# Backplane.net
KiCad netlist of a schematic drawn in EAGLE
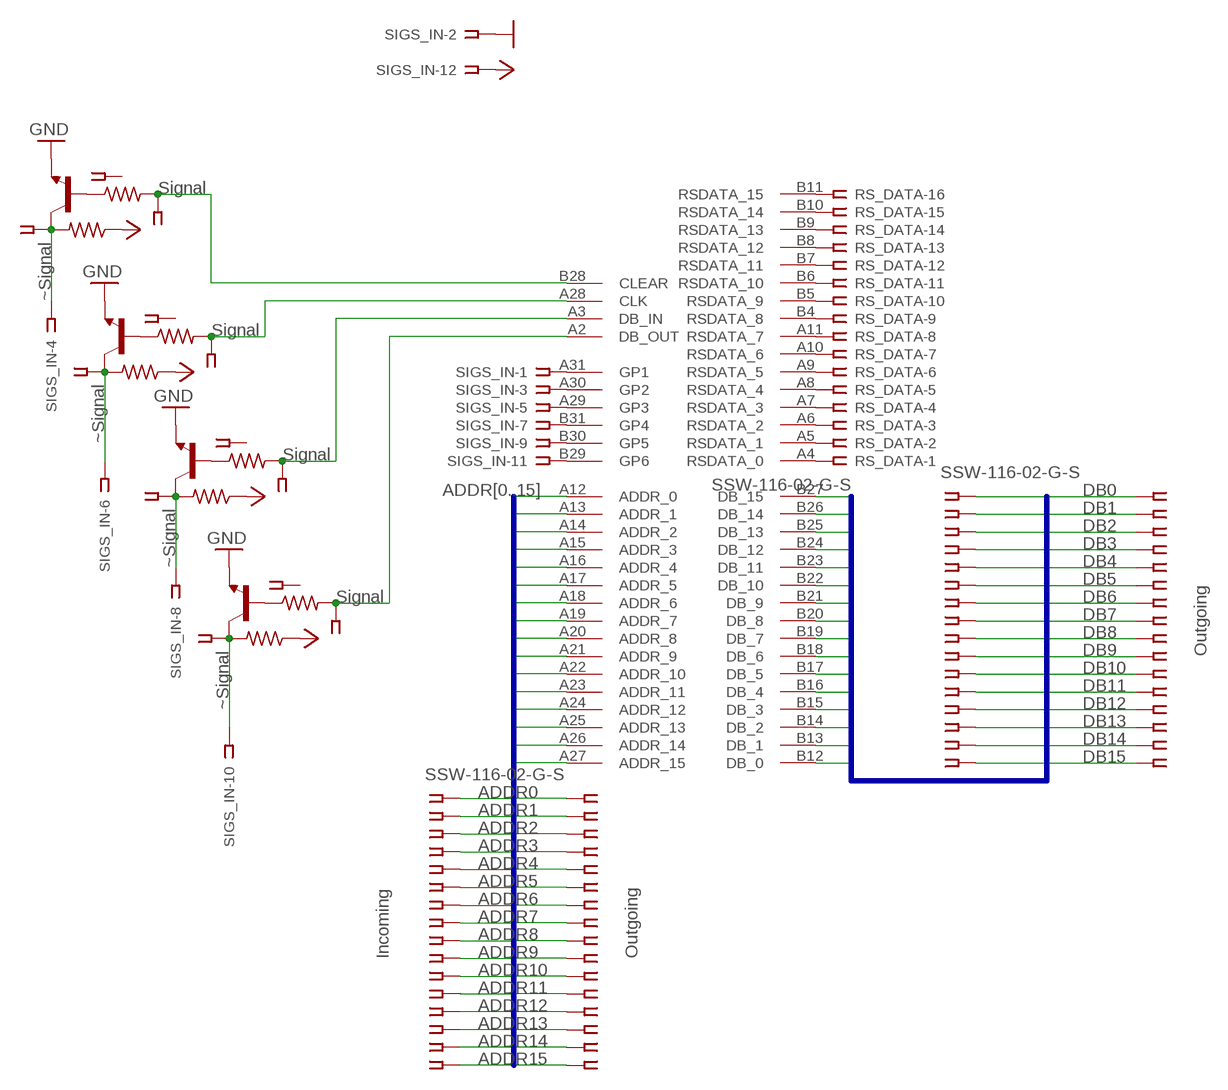
[diagram p0: schematic, sheet 1]

(export (version "E")
  (design (tool "Eeschema 10.0.6"))
  (components
    (comp (ref "ADDR_INCOMING")
      (value "SSW-116-02-G-S")
      (footprint "eagle-import:SSW-116-02-G-S")
      (fields (field (name "MF") "Samtec Inc."))
      (libsource (lib "eagle-import") (part "SSW-116-02-G-S"))
    )
    (comp (ref "ADDR_OUTGOING")
      (value "SSW-116-02-G-S-RA")
      (footprint "eagle-import:SSW-116-02-G-S-RA")
      (fields (field (name "MF") "Samtec Inc."))
      (libsource (lib "eagle-import") (part "SSW-116-02-G-S-RA"))
    )
    (comp (ref "DB_INCOMING")
      (value "SSW-116-02-G-S")
      (footprint "eagle-import:SSW-116-02-G-S")
      (fields (field (name "MF") "Samtec Inc."))
      (libsource (lib "eagle-import") (part "SSW-116-02-G-S"))
    )
    (comp (ref "DB_OUTGOING")
      (value "SSW-116-02-G-S-RA")
      (footprint "eagle-import:SSW-116-02-G-S-RA")
      (fields (field (name "MF") "Samtec Inc."))
      (libsource (lib "eagle-import") (part "SSW-116-02-G-S-RA"))
    )
    (comp (ref "NO_INVERT_JUMPER")
      (value "SSW-103-02-G-S")
      (footprint "eagle-import:SSW-103-02-G-S")
      (fields (field (name "MF") "Samtec Inc."))
      (libsource (lib "eagle-import") (part "SSW-103-02-G-S"))
    )
    (comp (ref "NO_INVERT_JUMPER1")
      (value "SSW-103-02-G-S")
      (footprint "eagle-import:SSW-103-02-G-S")
      (fields (field (name "MF") "Samtec Inc."))
      (libsource (lib "eagle-import") (part "SSW-103-02-G-S"))
    )
    (comp (ref "NO_INVERT_JUMPER2")
      (value "SSW-103-02-G-S")
      (footprint "eagle-import:SSW-103-02-G-S")
      (fields (field (name "MF") "Samtec Inc."))
      (libsource (lib "eagle-import") (part "SSW-103-02-G-S"))
    )
    (comp (ref "NO_INVERT_JUMPER3")
      (value "SSW-103-02-G-S")
      (footprint "eagle-import:SSW-103-02-G-S")
      (fields (field (name "MF") "Samtec Inc."))
      (libsource (lib "eagle-import") (part "SSW-103-02-G-S"))
    )
    (comp (ref "R1")
      (value "~220")
      (footprint "eagle-import:0204_7")
      (libsource (lib "eagle-import") (part "R-US_0204/7"))
    )
    (comp (ref "R2")
      (value "~220")
      (footprint "eagle-import:0204_7")
      (libsource (lib "eagle-import") (part "R-US_0204/7"))
    )
    (comp (ref "R3")
      (value "~220")
      (footprint "eagle-import:0204_7")
      (libsource (lib "eagle-import") (part "R-US_0204/7"))
    )
    (comp (ref "R4")
      (value "~220")
      (footprint "eagle-import:0204_7")
      (libsource (lib "eagle-import") (part "R-US_0204/7"))
    )
    (comp (ref "R5")
      (value "~220")
      (footprint "eagle-import:0204_7")
      (libsource (lib "eagle-import") (part "R-US_0204/7"))
    )
    (comp (ref "R6")
      (value "~220")
      (footprint "eagle-import:0204_7")
      (libsource (lib "eagle-import") (part "R-US_0204/7"))
    )
    (comp (ref "R7")
      (value "~220")
      (footprint "eagle-import:0204_7")
      (libsource (lib "eagle-import") (part "R-US_0204/7"))
    )
    (comp (ref "R8")
      (value "~220")
      (footprint "eagle-import:0204_7")
      (libsource (lib "eagle-import") (part "R-US_0204/7"))
    )
    (comp (ref "RS_DATA")
      (value "SSW-116-02-G-S")
      (footprint "eagle-import:SSW-116-02-G-S")
      (fields (field (name "MF") "Samtec Inc."))
      (libsource (lib "eagle-import") (part "SSW-116-02-G-S"))
    )
    (comp (ref "SIGS_IN")
      (value "SSW-106-02-G-D")
      (footprint "eagle-import:SSW-106-02-G-D")
      (fields (field (name "MF") "Samtec Inc."))
      (libsource (lib "eagle-import") (part "SSW-106-02-G-D"))
    )
    (comp (ref "T1")
      (value "2N3565")
      (footprint "eagle-import:TO92")
      (libsource (lib "eagle-import") (part "2N3565"))
    )
    (comp (ref "T2")
      (value "2N3565")
      (footprint "eagle-import:TO92")
      (libsource (lib "eagle-import") (part "2N3565"))
    )
    (comp (ref "T3")
      (value "2N3565")
      (footprint "eagle-import:TO92")
      (libsource (lib "eagle-import") (part "2N3565"))
    )
    (comp (ref "T4")
      (value "2N3565")
      (footprint "eagle-import:TO92")
      (libsource (lib "eagle-import") (part "2N3565"))
    )
    (comp (ref "U$1")
      (value "BACKPLATE_INTERFACEHEADER")
      (footprint "eagle-import:PCI_INTERFACE")
      (libsource (lib "eagle-import") (part "BACKPLATE_INTERFACEHEADER"))
    )
  )
  (nets
    (net (code "1") (name "/ADDR0") (class "Default")
      (node (ref "ADDR_INCOMING") (pin "1") (pinfunction "1_1") (pintype "passive"))
      (node (ref "ADDR_OUTGOING") (pin "16") (pinfunction "1_16") (pintype "passive"))
      (node (ref "U$1") (pin "A12") (pinfunction "ADDR_0_A12") (pintype "bidirectional"))
    )
    (net (code "2") (name "/ADDR1") (class "Default")
      (node (ref "ADDR_INCOMING") (pin "2") (pinfunction "1_2") (pintype "passive"))
      (node (ref "ADDR_OUTGOING") (pin "15") (pinfunction "1_15") (pintype "passive"))
      (node (ref "U$1") (pin "A13") (pinfunction "ADDR_1_A13") (pintype "bidirectional"))
    )
    (net (code "3") (name "/ADDR2") (class "Default")
      (node (ref "ADDR_INCOMING") (pin "3") (pinfunction "1_3") (pintype "passive"))
      (node (ref "ADDR_OUTGOING") (pin "14") (pinfunction "1_14") (pintype "passive"))
      (node (ref "U$1") (pin "A14") (pinfunction "ADDR_2_A14") (pintype "bidirectional"))
    )
    (net (code "4") (name "/ADDR3") (class "Default")
      (node (ref "ADDR_INCOMING") (pin "4") (pinfunction "1_4") (pintype "passive"))
      (node (ref "ADDR_OUTGOING") (pin "13") (pinfunction "1_13") (pintype "passive"))
      (node (ref "U$1") (pin "A15") (pinfunction "ADDR_3_A15") (pintype "bidirectional"))
    )
    (net (code "5") (name "/ADDR4") (class "Default")
      (node (ref "ADDR_INCOMING") (pin "5") (pinfunction "1_5") (pintype "passive"))
      (node (ref "ADDR_OUTGOING") (pin "12") (pinfunction "1_12") (pintype "passive"))
      (node (ref "U$1") (pin "A16") (pinfunction "ADDR_4_A16") (pintype "bidirectional"))
    )
    (net (code "6") (name "/ADDR5") (class "Default")
      (node (ref "ADDR_INCOMING") (pin "6") (pinfunction "1_6") (pintype "passive"))
      (node (ref "ADDR_OUTGOING") (pin "11") (pinfunction "1_11") (pintype "passive"))
      (node (ref "U$1") (pin "A17") (pinfunction "ADDR_5_A17") (pintype "bidirectional"))
    )
    (net (code "7") (name "/ADDR6") (class "Default")
      (node (ref "ADDR_INCOMING") (pin "7") (pinfunction "1_7") (pintype "passive"))
      (node (ref "ADDR_OUTGOING") (pin "10") (pinfunction "1_10") (pintype "passive"))
      (node (ref "U$1") (pin "A18") (pinfunction "ADDR_6_A18") (pintype "bidirectional"))
    )
    (net (code "8") (name "/ADDR7") (class "Default")
      (node (ref "ADDR_INCOMING") (pin "8") (pinfunction "1_8") (pintype "passive"))
      (node (ref "ADDR_OUTGOING") (pin "9") (pinfunction "1_9") (pintype "passive"))
      (node (ref "U$1") (pin "A19") (pinfunction "ADDR_7_A19") (pintype "bidirectional"))
    )
    (net (code "9") (name "/ADDR8") (class "Default")
      (node (ref "ADDR_INCOMING") (pin "9") (pinfunction "1_9") (pintype "passive"))
      (node (ref "ADDR_OUTGOING") (pin "8") (pinfunction "1_8") (pintype "passive"))
      (node (ref "U$1") (pin "A20") (pinfunction "ADDR_8_A20") (pintype "bidirectional"))
    )
    (net (code "10") (name "/ADDR9") (class "Default")
      (node (ref "ADDR_INCOMING") (pin "10") (pinfunction "1_10") (pintype "passive"))
      (node (ref "ADDR_OUTGOING") (pin "7") (pinfunction "1_7") (pintype "passive"))
      (node (ref "U$1") (pin "A21") (pinfunction "ADDR_9_A21") (pintype "bidirectional"))
    )
    (net (code "11") (name "/ADDR10") (class "Default")
      (node (ref "ADDR_INCOMING") (pin "11") (pinfunction "1_11") (pintype "passive"))
      (node (ref "ADDR_OUTGOING") (pin "6") (pinfunction "1_6") (pintype "passive"))
      (node (ref "U$1") (pin "A22") (pinfunction "ADDR_10_A22") (pintype "bidirectional"))
    )
    (net (code "12") (name "/ADDR11") (class "Default")
      (node (ref "ADDR_INCOMING") (pin "12") (pinfunction "1_12") (pintype "passive"))
      (node (ref "ADDR_OUTGOING") (pin "5") (pinfunction "1_5") (pintype "passive"))
      (node (ref "U$1") (pin "A23") (pinfunction "ADDR_11_A23") (pintype "bidirectional"))
    )
    (net (code "13") (name "/ADDR12") (class "Default")
      (node (ref "ADDR_INCOMING") (pin "13") (pinfunction "1_13") (pintype "passive"))
      (node (ref "ADDR_OUTGOING") (pin "4") (pinfunction "1_4") (pintype "passive"))
      (node (ref "U$1") (pin "A24") (pinfunction "ADDR_12_A24") (pintype "bidirectional"))
    )
    (net (code "14") (name "/ADDR13") (class "Default")
      (node (ref "ADDR_INCOMING") (pin "14") (pinfunction "1_14") (pintype "passive"))
      (node (ref "ADDR_OUTGOING") (pin "3") (pinfunction "1_3") (pintype "passive"))
      (node (ref "U$1") (pin "A25") (pinfunction "ADDR_13_A25") (pintype "bidirectional"))
    )
    (net (code "15") (name "/ADDR14") (class "Default")
      (node (ref "ADDR_INCOMING") (pin "15") (pinfunction "1_15") (pintype "passive"))
      (node (ref "ADDR_OUTGOING") (pin "2") (pinfunction "1_2") (pintype "passive"))
      (node (ref "U$1") (pin "A26") (pinfunction "ADDR_14_A26") (pintype "bidirectional"))
    )
    (net (code "16") (name "/ADDR15") (class "Default")
      (node (ref "ADDR_INCOMING") (pin "16") (pinfunction "1_16") (pintype "passive"))
      (node (ref "ADDR_OUTGOING") (pin "1") (pinfunction "1_1") (pintype "passive"))
      (node (ref "U$1") (pin "A27") (pinfunction "ADDR_15_A27") (pintype "bidirectional"))
    )
    (net (code "17") (name "/DB0") (class "Default")
      (node (ref "DB_INCOMING") (pin "1") (pinfunction "1_1") (pintype "passive"))
      (node (ref "DB_OUTGOING") (pin "16") (pinfunction "1_16") (pintype "passive"))
      (node (ref "U$1") (pin "B12") (pinfunction "DB_0_B12") (pintype "bidirectional"))
    )
    (net (code "18") (name "/DB1") (class "Default")
      (node (ref "DB_INCOMING") (pin "2") (pinfunction "1_2") (pintype "passive"))
      (node (ref "DB_OUTGOING") (pin "15") (pinfunction "1_15") (pintype "passive"))
      (node (ref "U$1") (pin "B13") (pinfunction "DB_1_B13") (pintype "bidirectional"))
    )
    (net (code "19") (name "/DB2") (class "Default")
      (node (ref "DB_INCOMING") (pin "3") (pinfunction "1_3") (pintype "passive"))
      (node (ref "DB_OUTGOING") (pin "14") (pinfunction "1_14") (pintype "passive"))
      (node (ref "U$1") (pin "B14") (pinfunction "DB_2_B14") (pintype "bidirectional"))
    )
    (net (code "20") (name "/DB3") (class "Default")
      (node (ref "DB_INCOMING") (pin "4") (pinfunction "1_4") (pintype "passive"))
      (node (ref "DB_OUTGOING") (pin "13") (pinfunction "1_13") (pintype "passive"))
      (node (ref "U$1") (pin "B15") (pinfunction "DB_3_B15") (pintype "bidirectional"))
    )
    (net (code "21") (name "/DB4") (class "Default")
      (node (ref "DB_INCOMING") (pin "5") (pinfunction "1_5") (pintype "passive"))
      (node (ref "DB_OUTGOING") (pin "12") (pinfunction "1_12") (pintype "passive"))
      (node (ref "U$1") (pin "B16") (pinfunction "DB_4_B16") (pintype "bidirectional"))
    )
    (net (code "22") (name "/DB5") (class "Default")
      (node (ref "DB_INCOMING") (pin "6") (pinfunction "1_6") (pintype "passive"))
      (node (ref "DB_OUTGOING") (pin "11") (pinfunction "1_11") (pintype "passive"))
      (node (ref "U$1") (pin "B17") (pinfunction "DB_5_B17") (pintype "bidirectional"))
    )
    (net (code "23") (name "/DB6") (class "Default")
      (node (ref "DB_INCOMING") (pin "7") (pinfunction "1_7") (pintype "passive"))
      (node (ref "DB_OUTGOING") (pin "10") (pinfunction "1_10") (pintype "passive"))
      (node (ref "U$1") (pin "B18") (pinfunction "DB_6_B18") (pintype "bidirectional"))
    )
    (net (code "24") (name "/DB7") (class "Default")
      (node (ref "DB_INCOMING") (pin "8") (pinfunction "1_8") (pintype "passive"))
      (node (ref "DB_OUTGOING") (pin "9") (pinfunction "1_9") (pintype "passive"))
      (node (ref "U$1") (pin "B19") (pinfunction "DB_7_B19") (pintype "bidirectional"))
    )
    (net (code "25") (name "/DB8") (class "Default")
      (node (ref "DB_INCOMING") (pin "9") (pinfunction "1_9") (pintype "passive"))
      (node (ref "DB_OUTGOING") (pin "8") (pinfunction "1_8") (pintype "passive"))
      (node (ref "U$1") (pin "B20") (pinfunction "DB_8_B20") (pintype "bidirectional"))
    )
    (net (code "26") (name "/DB9") (class "Default")
      (node (ref "DB_INCOMING") (pin "10") (pinfunction "1_10") (pintype "passive"))
      (node (ref "DB_OUTGOING") (pin "7") (pinfunction "1_7") (pintype "passive"))
      (node (ref "U$1") (pin "B21") (pinfunction "DB_9_B21") (pintype "bidirectional"))
    )
    (net (code "27") (name "/DB10") (class "Default")
      (node (ref "DB_INCOMING") (pin "11") (pinfunction "1_11") (pintype "passive"))
      (node (ref "DB_OUTGOING") (pin "6") (pinfunction "1_6") (pintype "passive"))
      (node (ref "U$1") (pin "B22") (pinfunction "DB_10_B22") (pintype "bidirectional"))
    )
    (net (code "28") (name "/DB11") (class "Default")
      (node (ref "DB_INCOMING") (pin "12") (pinfunction "1_12") (pintype "passive"))
      (node (ref "DB_OUTGOING") (pin "5") (pinfunction "1_5") (pintype "passive"))
      (node (ref "U$1") (pin "B23") (pinfunction "DB_11_B23") (pintype "bidirectional"))
    )
    (net (code "29") (name "/DB12") (class "Default")
      (node (ref "DB_INCOMING") (pin "13") (pinfunction "1_13") (pintype "passive"))
      (node (ref "DB_OUTGOING") (pin "4") (pinfunction "1_4") (pintype "passive"))
      (node (ref "U$1") (pin "B24") (pinfunction "DB_12_B24") (pintype "bidirectional"))
    )
    (net (code "30") (name "/DB13") (class "Default")
      (node (ref "DB_INCOMING") (pin "14") (pinfunction "1_14") (pintype "passive"))
      (node (ref "DB_OUTGOING") (pin "3") (pinfunction "1_3") (pintype "passive"))
      (node (ref "U$1") (pin "B25") (pinfunction "DB_13_B25") (pintype "bidirectional"))
    )
    (net (code "31") (name "/DB14") (class "Default")
      (node (ref "DB_INCOMING") (pin "15") (pinfunction "1_15") (pintype "passive"))
      (node (ref "DB_OUTGOING") (pin "2") (pinfunction "1_2") (pintype "passive"))
      (node (ref "U$1") (pin "B26") (pinfunction "DB_14_B26") (pintype "bidirectional"))
    )
    (net (code "32") (name "/DB15") (class "Default")
      (node (ref "DB_INCOMING") (pin "16") (pinfunction "1_16") (pintype "passive"))
      (node (ref "DB_OUTGOING") (pin "1") (pinfunction "1_1") (pintype "passive"))
      (node (ref "U$1") (pin "B27") (pinfunction "DB_15_B27") (pintype "bidirectional"))
    )
    (net (code "33") (name "GND") (class "Default")
      (node (ref "SIGS_IN") (pin "2") (pinfunction "1_2") (pintype "passive"))
      (node (ref "T1") (pin "3") (pinfunction "E_3") (pintype "passive"))
      (node (ref "T2") (pin "3") (pinfunction "E_3") (pintype "passive"))
      (node (ref "T3") (pin "3") (pinfunction "E_3") (pintype "passive"))
      (node (ref "T4") (pin "3") (pinfunction "E_3") (pintype "passive"))
    )
    (net (code "34") (name "Net-(NO_INVERT_JUMPER1B-1)") (class "Default")
      (node (ref "NO_INVERT_JUMPER1") (pin "2") (pinfunction "1_2") (pintype "passive"))
      (node (ref "R2") (pin "2") (pinfunction "2_2") (pintype "passive"))
      (node (ref "U$1") (pin "A28") (pinfunction "CLK_A28") (pintype "bidirectional"))
    )
    (net (code "35") (name "Net-(NO_INVERT_JUMPER1C-1)") (class "Default")
      (node (ref "NO_INVERT_JUMPER1") (pin "3") (pinfunction "1_3") (pintype "passive"))
      (node (ref "R3") (pin "2") (pinfunction "2_2") (pintype "passive"))
      (node (ref "SIGS_IN") (pin "6") (pinfunction "1_6") (pintype "passive"))
      (node (ref "T2") (pin "1") (pinfunction "C_1") (pintype "passive"))
    )
    (net (code "36") (name "Net-(NO_INVERT_JUMPER2B-1)") (class "Default")
      (node (ref "NO_INVERT_JUMPER2") (pin "2") (pinfunction "1_2") (pintype "passive"))
      (node (ref "R4") (pin "2") (pinfunction "2_2") (pintype "passive"))
      (node (ref "U$1") (pin "A3") (pinfunction "DB_IN_A3") (pintype "bidirectional"))
    )
    (net (code "37") (name "Net-(NO_INVERT_JUMPER2C-1)") (class "Default")
      (node (ref "NO_INVERT_JUMPER2") (pin "3") (pinfunction "1_3") (pintype "passive"))
      (node (ref "R5") (pin "2") (pinfunction "2_2") (pintype "passive"))
      (node (ref "SIGS_IN") (pin "8") (pinfunction "1_8") (pintype "passive"))
      (node (ref "T3") (pin "1") (pinfunction "C_1") (pintype "passive"))
    )
    (net (code "38") (name "Net-(NO_INVERT_JUMPER3B-1)") (class "Default")
      (node (ref "NO_INVERT_JUMPER3") (pin "2") (pinfunction "1_2") (pintype "passive"))
      (node (ref "R6") (pin "2") (pinfunction "2_2") (pintype "passive"))
      (node (ref "U$1") (pin "A2") (pinfunction "DB_OUT_A2") (pintype "bidirectional"))
    )
    (net (code "39") (name "Net-(NO_INVERT_JUMPER3C-1)") (class "Default")
      (node (ref "NO_INVERT_JUMPER3") (pin "3") (pinfunction "1_3") (pintype "passive"))
      (node (ref "R7") (pin "2") (pinfunction "2_2") (pintype "passive"))
      (node (ref "SIGS_IN") (pin "10") (pinfunction "1_10") (pintype "passive"))
      (node (ref "T4") (pin "1") (pinfunction "C_1") (pintype "passive"))
    )
    (net (code "40") (name "Net-(NO_INVERT_JUMPERB-1)") (class "Default")
      (node (ref "NO_INVERT_JUMPER") (pin "2") (pinfunction "1_2") (pintype "passive"))
      (node (ref "R8") (pin "2") (pinfunction "2_2") (pintype "passive"))
      (node (ref "U$1") (pin "B28") (pinfunction "CLEAR_B28") (pintype "bidirectional"))
    )
    (net (code "41") (name "Net-(NO_INVERT_JUMPERC-1)") (class "Default")
      (node (ref "NO_INVERT_JUMPER") (pin "3") (pinfunction "1_3") (pintype "passive"))
      (node (ref "R1") (pin "2") (pinfunction "2_2") (pintype "passive"))
      (node (ref "SIGS_IN") (pin "4") (pinfunction "1_4") (pintype "passive"))
      (node (ref "T1") (pin "1") (pinfunction "C_1") (pintype "passive"))
    )
    (net (code "42") (name "Net-(RS_DATAB-1)") (class "Default")
      (node (ref "RS_DATA") (pin "10") (pinfunction "1_10") (pintype "passive"))
      (node (ref "U$1") (pin "B5") (pinfunction "RSDATA_9_B5") (pintype "bidirectional"))
    )
    (net (code "43") (name "Net-(RS_DATAC-1)") (class "Default")
      (node (ref "RS_DATA") (pin "11") (pinfunction "1_11") (pintype "passive"))
      (node (ref "U$1") (pin "B6") (pinfunction "RSDATA_10_B6") (pintype "bidirectional"))
    )
    (net (code "44") (name "Net-(RS_DATAD-1)") (class "Default")
      (node (ref "RS_DATA") (pin "12") (pinfunction "1_12") (pintype "passive"))
      (node (ref "U$1") (pin "B7") (pinfunction "RSDATA_11_B7") (pintype "bidirectional"))
    )
    (net (code "45") (name "Net-(RS_DATAE-1)") (class "Default")
      (node (ref "RS_DATA") (pin "13") (pinfunction "1_13") (pintype "passive"))
      (node (ref "U$1") (pin "B8") (pinfunction "RSDATA_12_B8") (pintype "bidirectional"))
    )
    (net (code "46") (name "Net-(RS_DATAF-1)") (class "Default")
      (node (ref "RS_DATA") (pin "14") (pinfunction "1_14") (pintype "passive"))
      (node (ref "U$1") (pin "B9") (pinfunction "RSDATA_13_B9") (pintype "bidirectional"))
    )
    (net (code "47") (name "Net-(RS_DATAG-1)") (class "Default")
      (node (ref "RS_DATA") (pin "15") (pinfunction "1_15") (pintype "passive"))
      (node (ref "U$1") (pin "B10") (pinfunction "RSDATA_14_B10") (pintype "bidirectional"))
    )
    (net (code "48") (name "Net-(RS_DATAH-1)") (class "Default")
      (node (ref "RS_DATA") (pin "16") (pinfunction "1_16") (pintype "passive"))
      (node (ref "U$1") (pin "B11") (pinfunction "RSDATA_15_B11") (pintype "bidirectional"))
    )
    (net (code "49") (name "Net-(RS_DATAI-1)") (class "Default")
      (node (ref "RS_DATA") (pin "2") (pinfunction "1_2") (pintype "passive"))
      (node (ref "U$1") (pin "A5") (pinfunction "RSDATA_1_A5") (pintype "bidirectional"))
    )
    (net (code "50") (name "Net-(RS_DATAJ-1)") (class "Default")
      (node (ref "RS_DATA") (pin "3") (pinfunction "1_3") (pintype "passive"))
      (node (ref "U$1") (pin "A6") (pinfunction "RSDATA_2_A6") (pintype "bidirectional"))
    )
    (net (code "51") (name "Net-(RS_DATAK-1)") (class "Default")
      (node (ref "RS_DATA") (pin "4") (pinfunction "1_4") (pintype "passive"))
      (node (ref "U$1") (pin "A7") (pinfunction "RSDATA_3_A7") (pintype "bidirectional"))
    )
    (net (code "52") (name "Net-(RS_DATAL-1)") (class "Default")
      (node (ref "RS_DATA") (pin "5") (pinfunction "1_5") (pintype "passive"))
      (node (ref "U$1") (pin "A8") (pinfunction "RSDATA_4_A8") (pintype "bidirectional"))
    )
    (net (code "53") (name "Net-(RS_DATAM-1)") (class "Default")
      (node (ref "RS_DATA") (pin "6") (pinfunction "1_6") (pintype "passive"))
      (node (ref "U$1") (pin "A9") (pinfunction "RSDATA_5_A9") (pintype "bidirectional"))
    )
    (net (code "54") (name "Net-(RS_DATAN-1)") (class "Default")
      (node (ref "RS_DATA") (pin "7") (pinfunction "1_7") (pintype "passive"))
      (node (ref "U$1") (pin "A10") (pinfunction "RSDATA_6_A10") (pintype "bidirectional"))
    )
    (net (code "55") (name "Net-(RS_DATAO-1)") (class "Default")
      (node (ref "RS_DATA") (pin "8") (pinfunction "1_8") (pintype "passive"))
      (node (ref "U$1") (pin "A11") (pinfunction "RSDATA_7_A11") (pintype "bidirectional"))
    )
    (net (code "56") (name "Net-(RS_DATAP-1)") (class "Default")
      (node (ref "RS_DATA") (pin "9") (pinfunction "1_9") (pintype "passive"))
      (node (ref "U$1") (pin "B4") (pinfunction "RSDATA_8_B4") (pintype "bidirectional"))
    )
    (net (code "57") (name "Net-(SIGS_INC-1)") (class "Default")
      (node (ref "SIGS_IN") (pin "11") (pinfunction "1_11") (pintype "passive"))
      (node (ref "U$1") (pin "B29") (pinfunction "GP6_B29") (pintype "bidirectional"))
    )
    (net (code "58") (name "Net-(SIGS_INF-1)") (class "Default")
      (node (ref "SIGS_IN") (pin "3") (pinfunction "1_3") (pintype "passive"))
      (node (ref "U$1") (pin "A30") (pinfunction "GP2_A30") (pintype "bidirectional"))
    )
    (net (code "59") (name "Net-(SIGS_INH-1)") (class "Default")
      (node (ref "SIGS_IN") (pin "5") (pinfunction "1_5") (pintype "passive"))
      (node (ref "U$1") (pin "A29") (pinfunction "GP3_A29") (pintype "bidirectional"))
    )
    (net (code "60") (name "Net-(SIGS_INJ-1)") (class "Default")
      (node (ref "SIGS_IN") (pin "7") (pinfunction "1_7") (pintype "passive"))
      (node (ref "U$1") (pin "B31") (pinfunction "GP4_B31") (pintype "bidirectional"))
    )
    (net (code "61") (name "Net-(SIGS_INL-1)") (class "Default")
      (node (ref "SIGS_IN") (pin "9") (pinfunction "1_9") (pintype "passive"))
      (node (ref "U$1") (pin "B30") (pinfunction "GP5_B30") (pintype "bidirectional"))
    )
    (net (code "62") (name "Net-(T1-B)") (class "Default")
      (node (ref "R8") (pin "1") (pinfunction "1_1") (pintype "passive"))
      (node (ref "T1") (pin "2") (pinfunction "B_2") (pintype "passive"))
    )
    (net (code "63") (name "Net-(T2-B)") (class "Default")
      (node (ref "R2") (pin "1") (pinfunction "1_1") (pintype "passive"))
      (node (ref "T2") (pin "2") (pinfunction "B_2") (pintype "passive"))
    )
    (net (code "64") (name "Net-(T3-B)") (class "Default")
      (node (ref "R4") (pin "1") (pinfunction "1_1") (pintype "passive"))
      (node (ref "T3") (pin "2") (pinfunction "B_2") (pintype "passive"))
    )
    (net (code "65") (name "Net-(T4-B)") (class "Default")
      (node (ref "R6") (pin "1") (pinfunction "1_1") (pintype "passive"))
      (node (ref "T4") (pin "2") (pinfunction "B_2") (pintype "passive"))
    )
    (net (code "66") (name "Net-(U$1A-GP1)") (class "Default")
      (node (ref "SIGS_IN") (pin "1") (pinfunction "1_1") (pintype "passive"))
      (node (ref "U$1") (pin "A31") (pinfunction "GP1_A31") (pintype "bidirectional"))
    )
    (net (code "67") (name "Net-(U$1A-RSDATA_0)") (class "Default")
      (node (ref "RS_DATA") (pin "1") (pinfunction "1_1") (pintype "passive"))
      (node (ref "U$1") (pin "A4") (pinfunction "RSDATA_0_A4") (pintype "bidirectional"))
    )
    (net (code "68") (name "VCC") (class "Default")
      (node (ref "R1") (pin "1") (pinfunction "1_1") (pintype "passive"))
      (node (ref "R3") (pin "1") (pinfunction "1_1") (pintype "passive"))
      (node (ref "R5") (pin "1") (pinfunction "1_1") (pintype "passive"))
      (node (ref "R7") (pin "1") (pinfunction "1_1") (pintype "passive"))
      (node (ref "SIGS_IN") (pin "12") (pinfunction "1_12") (pintype "passive"))
    )
    (net (code "69") (name "unconnected-(NO_INVERT_JUMPER-Pad1)") (class "Default")
      (node (ref "NO_INVERT_JUMPER") (pin "1") (pinfunction "1_1") (pintype "passive"))
    )
    (net (code "70") (name "unconnected-(NO_INVERT_JUMPER1-Pad1)") (class "Default")
      (node (ref "NO_INVERT_JUMPER1") (pin "1") (pinfunction "1_1") (pintype "passive"))
    )
    (net (code "71") (name "unconnected-(NO_INVERT_JUMPER2-Pad1)") (class "Default")
      (node (ref "NO_INVERT_JUMPER2") (pin "1") (pinfunction "1_1") (pintype "passive"))
    )
    (net (code "72") (name "unconnected-(NO_INVERT_JUMPER3-Pad1)") (class "Default")
      (node (ref "NO_INVERT_JUMPER3") (pin "1") (pinfunction "1_1") (pintype "passive"))
    )
  )
)
